# RotaryEncoderModule_r1_2.net
KiCad netlist of a schematic drawn in EAGLE
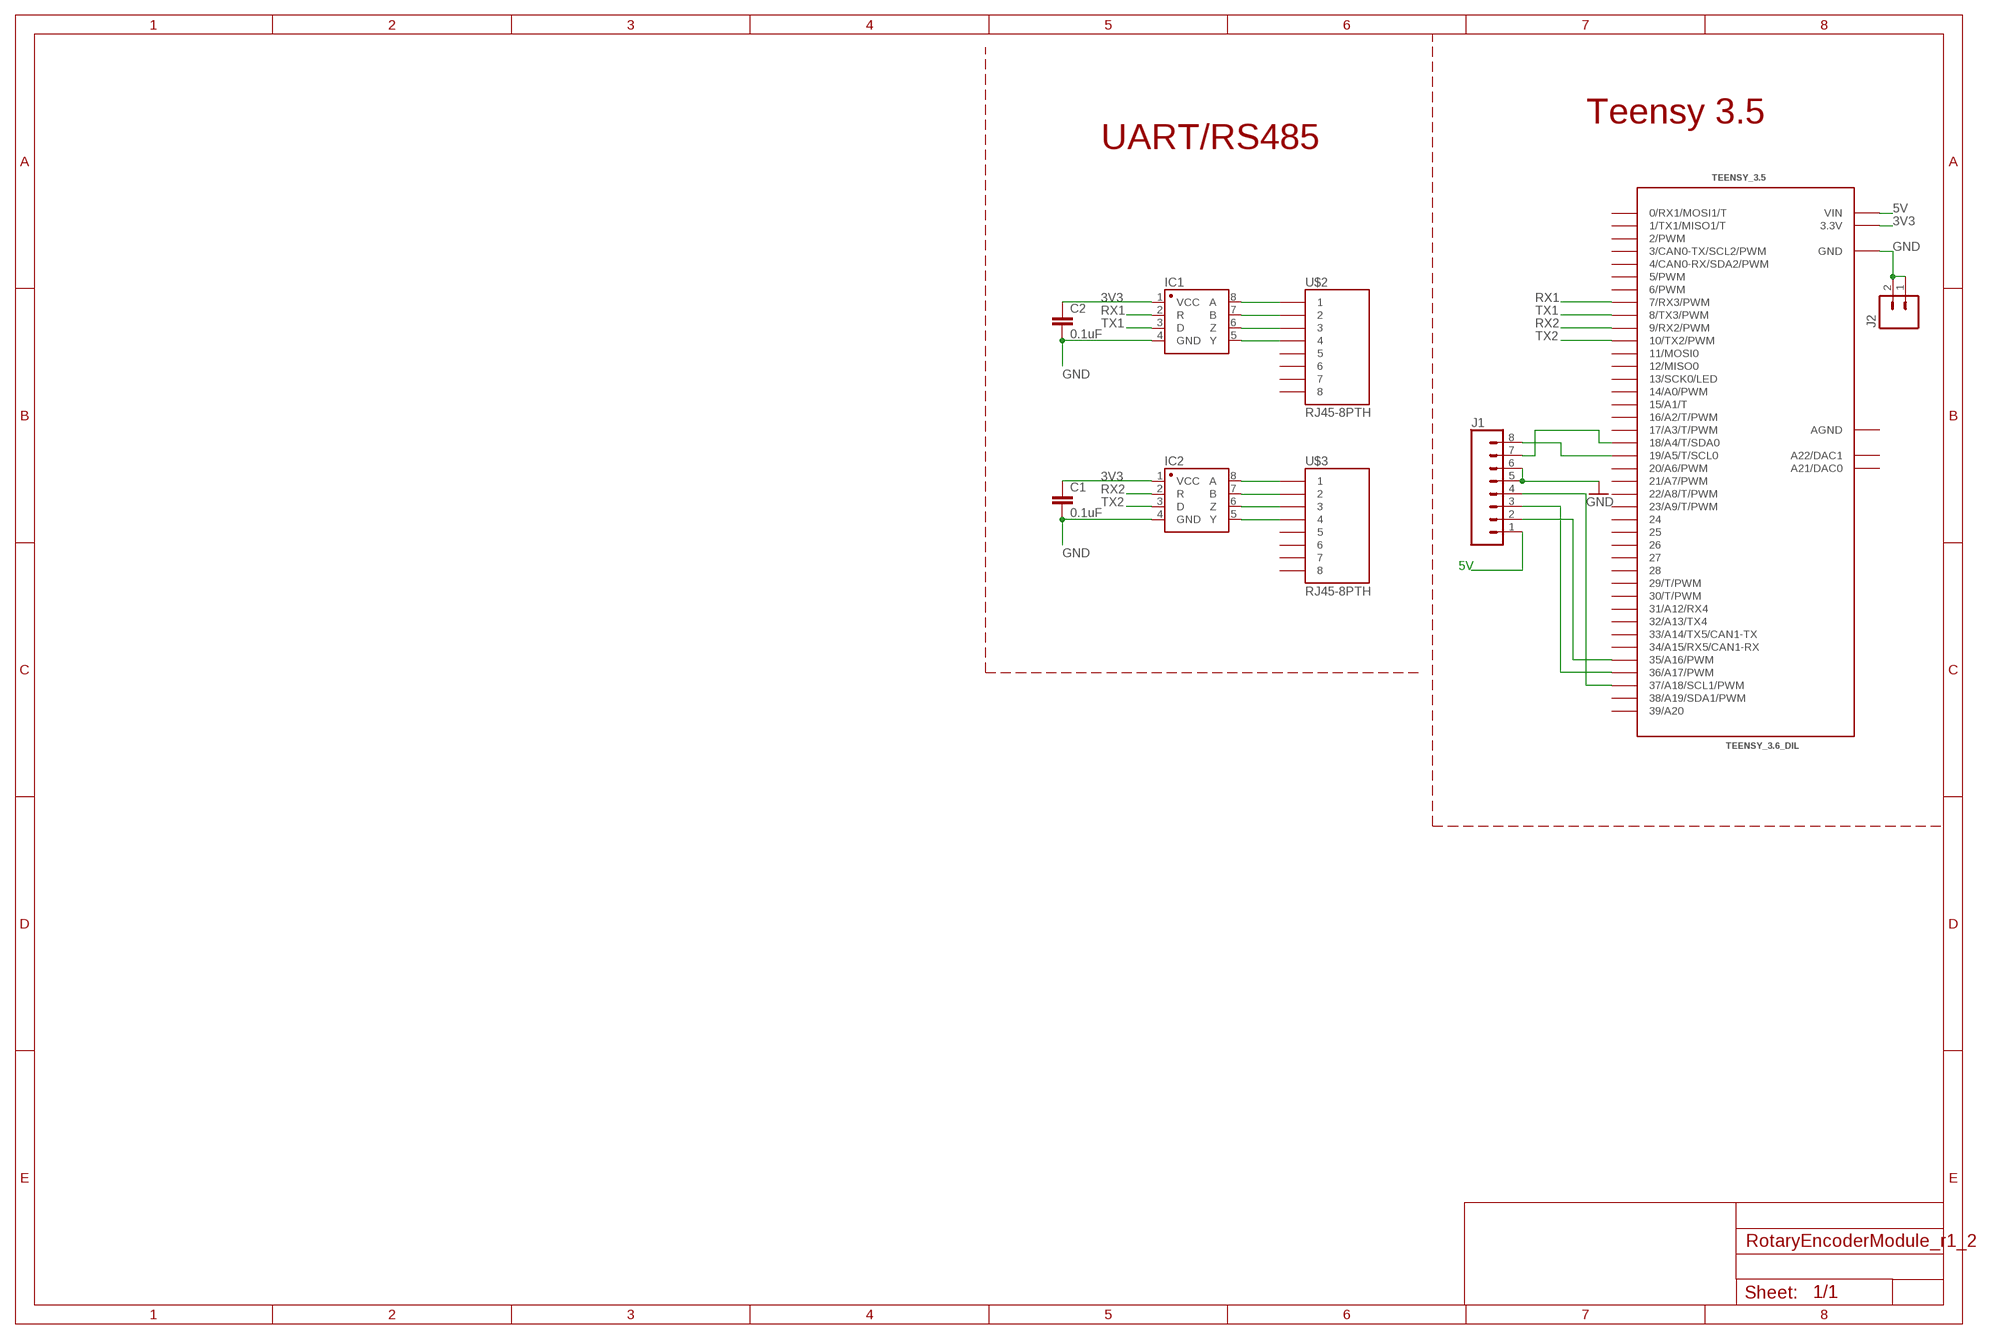
[diagram p0: schematic, sheet 1]

(export (version "E")
  (design (tool "Eeschema 10.0.6"))
  (components
    (comp (ref "C1")
      (value "0.1uF")
      (footprint "eagle-import:1206")
      (libsource (lib "eagle-import") (part "1.0UF-1206-50V-10%"))
    )
    (comp (ref "C2")
      (value "0.1uF")
      (footprint "eagle-import:1206")
      (libsource (lib "eagle-import") (part "1.0UF-1206-50V-10%"))
    )
    (comp (ref "IC1")
      (value "SN65HVD31DR")
      (footprint "eagle-import:SO08")
      (libsource (lib "eagle-import") (part "SN65HVD31DR"))
    )
    (comp (ref "IC2")
      (value "SN65HVD31DR")
      (footprint "eagle-import:SO08")
      (libsource (lib "eagle-import") (part "SN65HVD31DR"))
    )
    (comp (ref "J1")
      (value "CONN_083.5MM-8")
      (footprint "eagle-import:SCREWTERMINAL-3.5MM-8")
      (libsource (lib "eagle-import") (part "CONN_083.5MM-8"))
    )
    (comp (ref "J2")
      (value "M023.5MM")
      (footprint "eagle-import:SCREWTERMINAL-3.5MM-2")
      (libsource (lib "eagle-import") (part "M023.5MM"))
    )
    (comp (ref "TEENSY_3.5")
      (value "TEENSY_3.6_DIL")
      (footprint "eagle-import:TEENSY_3.6_DIL")
      (libsource (lib "eagle-import") (part "TEENSY_3.6_DIL"))
    )
    (comp (ref "U$2")
      (value "RJ45-8PTH")
      (footprint "eagle-import:RJ45-8")
      (libsource (lib "eagle-import") (part "RJ45-8PTH"))
    )
    (comp (ref "U$3")
      (value "RJ45-8PTH")
      (footprint "eagle-import:RJ45-8")
      (libsource (lib "eagle-import") (part "RJ45-8PTH"))
    )
  )
  (nets
    (net (code "1") (name "/3V3") (class "Default")
      (node (ref "C1") (pin "1") (pinfunction "1_1") (pintype "passive"))
      (node (ref "C2") (pin "1") (pinfunction "1_1") (pintype "passive"))
      (node (ref "IC1") (pin "1") (pinfunction "VCC_1") (pintype "bidirectional"))
      (node (ref "IC2") (pin "1") (pinfunction "VCC_1") (pintype "bidirectional"))
      (node (ref "TEENSY_3.5") (pin "3.3V") (pinfunction "3.3V_3.3V") (pintype "power_in"))
      (node (ref "TEENSY_3.5") (pin "3.3V3") (pinfunction "3.3V_3.3V3") (pintype "power_in"))
    )
    (net (code "2") (name "/5V") (class "Default")
      (node (ref "J1") (pin "1") (pinfunction "1_1") (pintype "passive"))
      (node (ref "TEENSY_3.5") (pin "VIN") (pinfunction "VIN_VIN") (pintype "power_in"))
    )
    (net (code "3") (name "/AGND") (class "Default")
      (node (ref "TEENSY_3.5") (pin "AGND") (pinfunction "AGND_AGND") (pintype "power_in"))
    )
    (net (code "4") (name "/RX1") (class "Default")
      (node (ref "IC1") (pin "2") (pinfunction "R_2") (pintype "bidirectional"))
      (node (ref "TEENSY_3.5") (pin "7") (pinfunction "7/RX3/PWM_7") (pintype "bidirectional"))
    )
    (net (code "5") (name "/RX2") (class "Default")
      (node (ref "IC2") (pin "2") (pinfunction "R_2") (pintype "bidirectional"))
      (node (ref "TEENSY_3.5") (pin "9") (pinfunction "9/RX2/PWM_9") (pintype "bidirectional"))
    )
    (net (code "6") (name "/TX1") (class "Default")
      (node (ref "IC1") (pin "3") (pinfunction "D_3") (pintype "bidirectional"))
      (node (ref "TEENSY_3.5") (pin "8") (pinfunction "8/TX3/PWM_8") (pintype "bidirectional"))
    )
    (net (code "7") (name "/TX2") (class "Default")
      (node (ref "IC2") (pin "3") (pinfunction "D_3") (pintype "bidirectional"))
      (node (ref "TEENSY_3.5") (pin "10") (pinfunction "10/TX2/PWM_10") (pintype "bidirectional"))
    )
    (net (code "8") (name "GND") (class "Default")
      (node (ref "C1") (pin "2") (pinfunction "2_2") (pintype "passive"))
      (node (ref "C2") (pin "2") (pinfunction "2_2") (pintype "passive"))
      (node (ref "IC1") (pin "4") (pinfunction "GND_4") (pintype "bidirectional"))
      (node (ref "IC2") (pin "4") (pinfunction "GND_4") (pintype "bidirectional"))
      (node (ref "J1") (pin "5") (pinfunction "5_5") (pintype "passive"))
      (node (ref "J1") (pin "6") (pinfunction "6_6") (pintype "passive"))
      (node (ref "J2") (pin "1") (pinfunction "1_1") (pintype "passive"))
      (node (ref "J2") (pin "2") (pinfunction "2_2") (pintype "passive"))
      (node (ref "TEENSY_3.5") (pin "GND") (pinfunction "GND_GND") (pintype "power_in"))
      (node (ref "TEENSY_3.5") (pin "GND1") (pinfunction "GND_GND1") (pintype "power_in"))
    )
    (net (code "9") (name "Net-(IC1-A)") (class "Default")
      (node (ref "IC1") (pin "8") (pinfunction "A_8") (pintype "bidirectional"))
      (node (ref "U$2") (pin "1") (pinfunction "1_1") (pintype "bidirectional"))
    )
    (net (code "10") (name "Net-(IC1-B)") (class "Default")
      (node (ref "IC1") (pin "7") (pinfunction "B_7") (pintype "bidirectional"))
      (node (ref "U$2") (pin "2") (pinfunction "2_2") (pintype "bidirectional"))
    )
    (net (code "11") (name "Net-(IC1-Y)") (class "Default")
      (node (ref "IC1") (pin "5") (pinfunction "Y_5") (pintype "bidirectional"))
      (node (ref "U$2") (pin "4") (pinfunction "4_4") (pintype "bidirectional"))
    )
    (net (code "12") (name "Net-(IC1-Z)") (class "Default")
      (node (ref "IC1") (pin "6") (pinfunction "Z_6") (pintype "bidirectional"))
      (node (ref "U$2") (pin "3") (pinfunction "3_3") (pintype "bidirectional"))
    )
    (net (code "13") (name "Net-(IC2-A)") (class "Default")
      (node (ref "IC2") (pin "8") (pinfunction "A_8") (pintype "bidirectional"))
      (node (ref "U$3") (pin "1") (pinfunction "1_1") (pintype "bidirectional"))
    )
    (net (code "14") (name "Net-(IC2-B)") (class "Default")
      (node (ref "IC2") (pin "7") (pinfunction "B_7") (pintype "bidirectional"))
      (node (ref "U$3") (pin "2") (pinfunction "2_2") (pintype "bidirectional"))
    )
    (net (code "15") (name "Net-(IC2-Y)") (class "Default")
      (node (ref "IC2") (pin "5") (pinfunction "Y_5") (pintype "bidirectional"))
      (node (ref "U$3") (pin "4") (pinfunction "4_4") (pintype "bidirectional"))
    )
    (net (code "16") (name "Net-(IC2-Z)") (class "Default")
      (node (ref "IC2") (pin "6") (pinfunction "Z_6") (pintype "bidirectional"))
      (node (ref "U$3") (pin "3") (pinfunction "3_3") (pintype "bidirectional"))
    )
    (net (code "17") (name "Net-(TEENSY_3.5-18{slash}A4{slash}T{slash}SDA0)") (class "Default")
      (node (ref "J1") (pin "7") (pinfunction "7_7") (pintype "passive"))
      (node (ref "TEENSY_3.5") (pin "18/A4") (pinfunction "18/A4/T/SDA0_18/A4") (pintype "bidirectional"))
    )
    (net (code "18") (name "Net-(TEENSY_3.5-19{slash}A5{slash}T{slash}SCL0)") (class "Default")
      (node (ref "J1") (pin "8") (pinfunction "8_8") (pintype "passive"))
      (node (ref "TEENSY_3.5") (pin "19/A5") (pinfunction "19/A5/T/SCL0_19/A5") (pintype "bidirectional"))
    )
    (net (code "19") (name "Net-(TEENSY_3.5-35{slash}A16{slash}PWM)") (class "Default")
      (node (ref "J1") (pin "2") (pinfunction "2_2") (pintype "passive"))
      (node (ref "TEENSY_3.5") (pin "35/A16") (pinfunction "35/A16/PWM_35/A16") (pintype "bidirectional"))
    )
    (net (code "20") (name "Net-(TEENSY_3.5-36{slash}A17{slash}PWM)") (class "Default")
      (node (ref "J1") (pin "3") (pinfunction "3_3") (pintype "passive"))
      (node (ref "TEENSY_3.5") (pin "36/A17") (pinfunction "36/A17/PWM_36/A17") (pintype "bidirectional"))
    )
    (net (code "21") (name "Net-(TEENSY_3.5-37{slash}A18{slash}SCL1{slash}PWM)") (class "Default")
      (node (ref "J1") (pin "4") (pinfunction "4_4") (pintype "passive"))
      (node (ref "TEENSY_3.5") (pin "37/A18") (pinfunction "37/A18/SCL1/PWM_37/A18") (pintype "bidirectional"))
    )
    (net (code "22") (name "unconnected-(TEENSY_3.5-0{slash}RX1{slash}MOSI1{slash}T-Pad0)") (class "Default")
      (node (ref "TEENSY_3.5") (pin "0") (pinfunction "0/RX1/MOSI1/T_0") (pintype "bidirectional"))
    )
    (net (code "23") (name "unconnected-(TEENSY_3.5-1{slash}TX1{slash}MISO1{slash}T-Pad1)") (class "Default")
      (node (ref "TEENSY_3.5") (pin "1") (pinfunction "1/TX1/MISO1/T_1") (pintype "bidirectional"))
    )
    (net (code "24") (name "unconnected-(TEENSY_3.5-2{slash}PWM-Pad2)") (class "Default")
      (node (ref "TEENSY_3.5") (pin "2") (pinfunction "2/PWM_2") (pintype "bidirectional"))
    )
    (net (code "25") (name "unconnected-(TEENSY_3.5-3{slash}CAN0-TX{slash}SCL2{slash}PWM-Pad3)") (class "Default")
      (node (ref "TEENSY_3.5") (pin "3") (pinfunction "3/CAN0-TX/SCL2/PWM_3") (pintype "bidirectional"))
    )
    (net (code "26") (name "unconnected-(TEENSY_3.5-4{slash}CAN0-RX{slash}SDA2{slash}PWM-Pad4)") (class "Default")
      (node (ref "TEENSY_3.5") (pin "4") (pinfunction "4/CAN0-RX/SDA2/PWM_4") (pintype "bidirectional"))
    )
    (net (code "27") (name "unconnected-(TEENSY_3.5-5{slash}PWM-Pad5)") (class "Default")
      (node (ref "TEENSY_3.5") (pin "5") (pinfunction "5/PWM_5") (pintype "bidirectional"))
    )
    (net (code "28") (name "unconnected-(TEENSY_3.5-6{slash}PWM-Pad6)") (class "Default")
      (node (ref "TEENSY_3.5") (pin "6") (pinfunction "6/PWM_6") (pintype "bidirectional"))
    )
    (net (code "29") (name "unconnected-(TEENSY_3.5-11{slash}MOSI0-Pad11)") (class "Default")
      (node (ref "TEENSY_3.5") (pin "11") (pinfunction "11/MOSI0_11") (pintype "bidirectional"))
    )
    (net (code "30") (name "unconnected-(TEENSY_3.5-12{slash}MISO0-Pad12)") (class "Default")
      (node (ref "TEENSY_3.5") (pin "12") (pinfunction "12/MISO0_12") (pintype "bidirectional"))
    )
    (net (code "31") (name "unconnected-(TEENSY_3.5-13{slash}SCK0{slash}LED-Pad13)") (class "Default")
      (node (ref "TEENSY_3.5") (pin "13") (pinfunction "13/SCK0/LED_13") (pintype "bidirectional"))
    )
    (net (code "32") (name "unconnected-(TEENSY_3.5-14{slash}A0{slash}PWM-Pad14{slash}A0)") (class "Default")
      (node (ref "TEENSY_3.5") (pin "14/A0") (pinfunction "14/A0/PWM_14/A0") (pintype "bidirectional"))
    )
    (net (code "33") (name "unconnected-(TEENSY_3.5-15{slash}A1{slash}T-Pad15{slash}A1)") (class "Default")
      (node (ref "TEENSY_3.5") (pin "15/A1") (pinfunction "15/A1/T_15/A1") (pintype "bidirectional"))
    )
    (net (code "34") (name "unconnected-(TEENSY_3.5-16{slash}A2{slash}T{slash}PWM-Pad16{slash}A2)") (class "Default")
      (node (ref "TEENSY_3.5") (pin "16/A2") (pinfunction "16/A2/T/PWM_16/A2") (pintype "bidirectional"))
    )
    (net (code "35") (name "unconnected-(TEENSY_3.5-17{slash}A3{slash}T{slash}PWM-Pad17{slash}A3)") (class "Default")
      (node (ref "TEENSY_3.5") (pin "17/A3") (pinfunction "17/A3/T/PWM_17/A3") (pintype "bidirectional"))
    )
    (net (code "36") (name "unconnected-(TEENSY_3.5-20{slash}A6{slash}PWM-Pad20{slash}A6)") (class "Default")
      (node (ref "TEENSY_3.5") (pin "20/A6") (pinfunction "20/A6/PWM_20/A6") (pintype "bidirectional"))
    )
    (net (code "37") (name "unconnected-(TEENSY_3.5-21{slash}A7{slash}PWM-Pad21{slash}A7)") (class "Default")
      (node (ref "TEENSY_3.5") (pin "21/A7") (pinfunction "21/A7/PWM_21/A7") (pintype "bidirectional"))
    )
    (net (code "38") (name "unconnected-(TEENSY_3.5-22{slash}A8{slash}T{slash}PWM-Pad22{slash}A8)") (class "Default")
      (node (ref "TEENSY_3.5") (pin "22/A8") (pinfunction "22/A8/T/PWM_22/A8") (pintype "bidirectional"))
    )
    (net (code "39") (name "unconnected-(TEENSY_3.5-23{slash}A9{slash}T{slash}PWM-Pad23{slash}A9)") (class "Default")
      (node (ref "TEENSY_3.5") (pin "23/A9") (pinfunction "23/A9/T/PWM_23/A9") (pintype "bidirectional"))
    )
    (net (code "40") (name "unconnected-(TEENSY_3.5-29{slash}T{slash}PWM-Pad29)") (class "Default")
      (node (ref "TEENSY_3.5") (pin "29") (pinfunction "29/T/PWM_29") (pintype "bidirectional"))
    )
    (net (code "41") (name "unconnected-(TEENSY_3.5-30{slash}T{slash}PWM-Pad30)") (class "Default")
      (node (ref "TEENSY_3.5") (pin "30") (pinfunction "30/T/PWM_30") (pintype "bidirectional"))
    )
    (net (code "42") (name "unconnected-(TEENSY_3.5-31{slash}A12{slash}RX4-Pad31{slash}A12)") (class "Default")
      (node (ref "TEENSY_3.5") (pin "31/A12") (pinfunction "31/A12/RX4_31/A12") (pintype "bidirectional"))
    )
    (net (code "43") (name "unconnected-(TEENSY_3.5-32{slash}A13{slash}TX4-Pad32{slash}A13)") (class "Default")
      (node (ref "TEENSY_3.5") (pin "32/A13") (pinfunction "32/A13/TX4_32/A13") (pintype "bidirectional"))
    )
    (net (code "44") (name "unconnected-(TEENSY_3.5-33{slash}A14{slash}TX5{slash}CAN1-TX-Pad33{slash}A14)") (class "Default")
      (node (ref "TEENSY_3.5") (pin "33/A14") (pinfunction "33/A14/TX5/CAN1-TX_33/A14") (pintype "bidirectional"))
    )
    (net (code "45") (name "unconnected-(TEENSY_3.5-34{slash}A15{slash}RX5{slash}CAN1-RX-Pad34{slash}A15)") (class "Default")
      (node (ref "TEENSY_3.5") (pin "34/A15") (pinfunction "34/A15/RX5/CAN1-RX_34/A15") (pintype "bidirectional"))
    )
    (net (code "46") (name "unconnected-(TEENSY_3.5-38{slash}A19{slash}SDA1{slash}PWM-Pad38{slash}A19)") (class "Default")
      (node (ref "TEENSY_3.5") (pin "38/A19") (pinfunction "38/A19/SDA1/PWM_38/A19") (pintype "bidirectional"))
    )
    (net (code "47") (name "unconnected-(TEENSY_3.5-A21{slash}DAC0-PadA21)") (class "Default")
      (node (ref "TEENSY_3.5") (pin "A21") (pinfunction "A21/DAC0_A21") (pintype "bidirectional"))
    )
    (net (code "48") (name "unconnected-(TEENSY_3.5-A22{slash}DAC1-PadA22)") (class "Default")
      (node (ref "TEENSY_3.5") (pin "A22") (pinfunction "A22/DAC1_A22") (pintype "bidirectional"))
    )
    (net (code "49") (name "unconnected-(TEENSY_3.5-Pad24)") (class "Default")
      (node (ref "TEENSY_3.5") (pin "24") (pinfunction "24_24") (pintype "bidirectional"))
    )
    (net (code "50") (name "unconnected-(TEENSY_3.5-Pad25)") (class "Default")
      (node (ref "TEENSY_3.5") (pin "25") (pinfunction "25_25") (pintype "bidirectional"))
    )
    (net (code "51") (name "unconnected-(TEENSY_3.5-Pad26)") (class "Default")
      (node (ref "TEENSY_3.5") (pin "26") (pinfunction "26_26") (pintype "bidirectional"))
    )
    (net (code "52") (name "unconnected-(TEENSY_3.5-Pad27)") (class "Default")
      (node (ref "TEENSY_3.5") (pin "27") (pinfunction "27_27") (pintype "bidirectional"))
    )
    (net (code "53") (name "unconnected-(TEENSY_3.5-Pad28)") (class "Default")
      (node (ref "TEENSY_3.5") (pin "28") (pinfunction "28_28") (pintype "bidirectional"))
    )
    (net (code "54") (name "unconnected-(TEENSY_3.5-Pad39{slash}A20)") (class "Default")
      (node (ref "TEENSY_3.5") (pin "39/A20") (pinfunction "39/A20_39/A20") (pintype "bidirectional"))
    )
    (net (code "55") (name "unconnected-(U$2-Pad5)") (class "Default")
      (node (ref "U$2") (pin "5") (pinfunction "5_5") (pintype "bidirectional"))
    )
    (net (code "56") (name "unconnected-(U$2-Pad6)") (class "Default")
      (node (ref "U$2") (pin "6") (pinfunction "6_6") (pintype "bidirectional"))
    )
    (net (code "57") (name "unconnected-(U$2-Pad7)") (class "Default")
      (node (ref "U$2") (pin "7") (pinfunction "7_7") (pintype "bidirectional"))
    )
    (net (code "58") (name "unconnected-(U$2-Pad8)") (class "Default")
      (node (ref "U$2") (pin "8") (pinfunction "8_8") (pintype "bidirectional"))
    )
    (net (code "59") (name "unconnected-(U$3-Pad5)") (class "Default")
      (node (ref "U$3") (pin "5") (pinfunction "5_5") (pintype "bidirectional"))
    )
    (net (code "60") (name "unconnected-(U$3-Pad6)") (class "Default")
      (node (ref "U$3") (pin "6") (pinfunction "6_6") (pintype "bidirectional"))
    )
    (net (code "61") (name "unconnected-(U$3-Pad7)") (class "Default")
      (node (ref "U$3") (pin "7") (pinfunction "7_7") (pintype "bidirectional"))
    )
    (net (code "62") (name "unconnected-(U$3-Pad8)") (class "Default")
      (node (ref "U$3") (pin "8") (pinfunction "8_8") (pintype "bidirectional"))
    )
  )
)
